# Adafruit_0_96in_128x64_OLED_STEMMA_QT.net
KiCad netlist of a schematic drawn in EAGLE
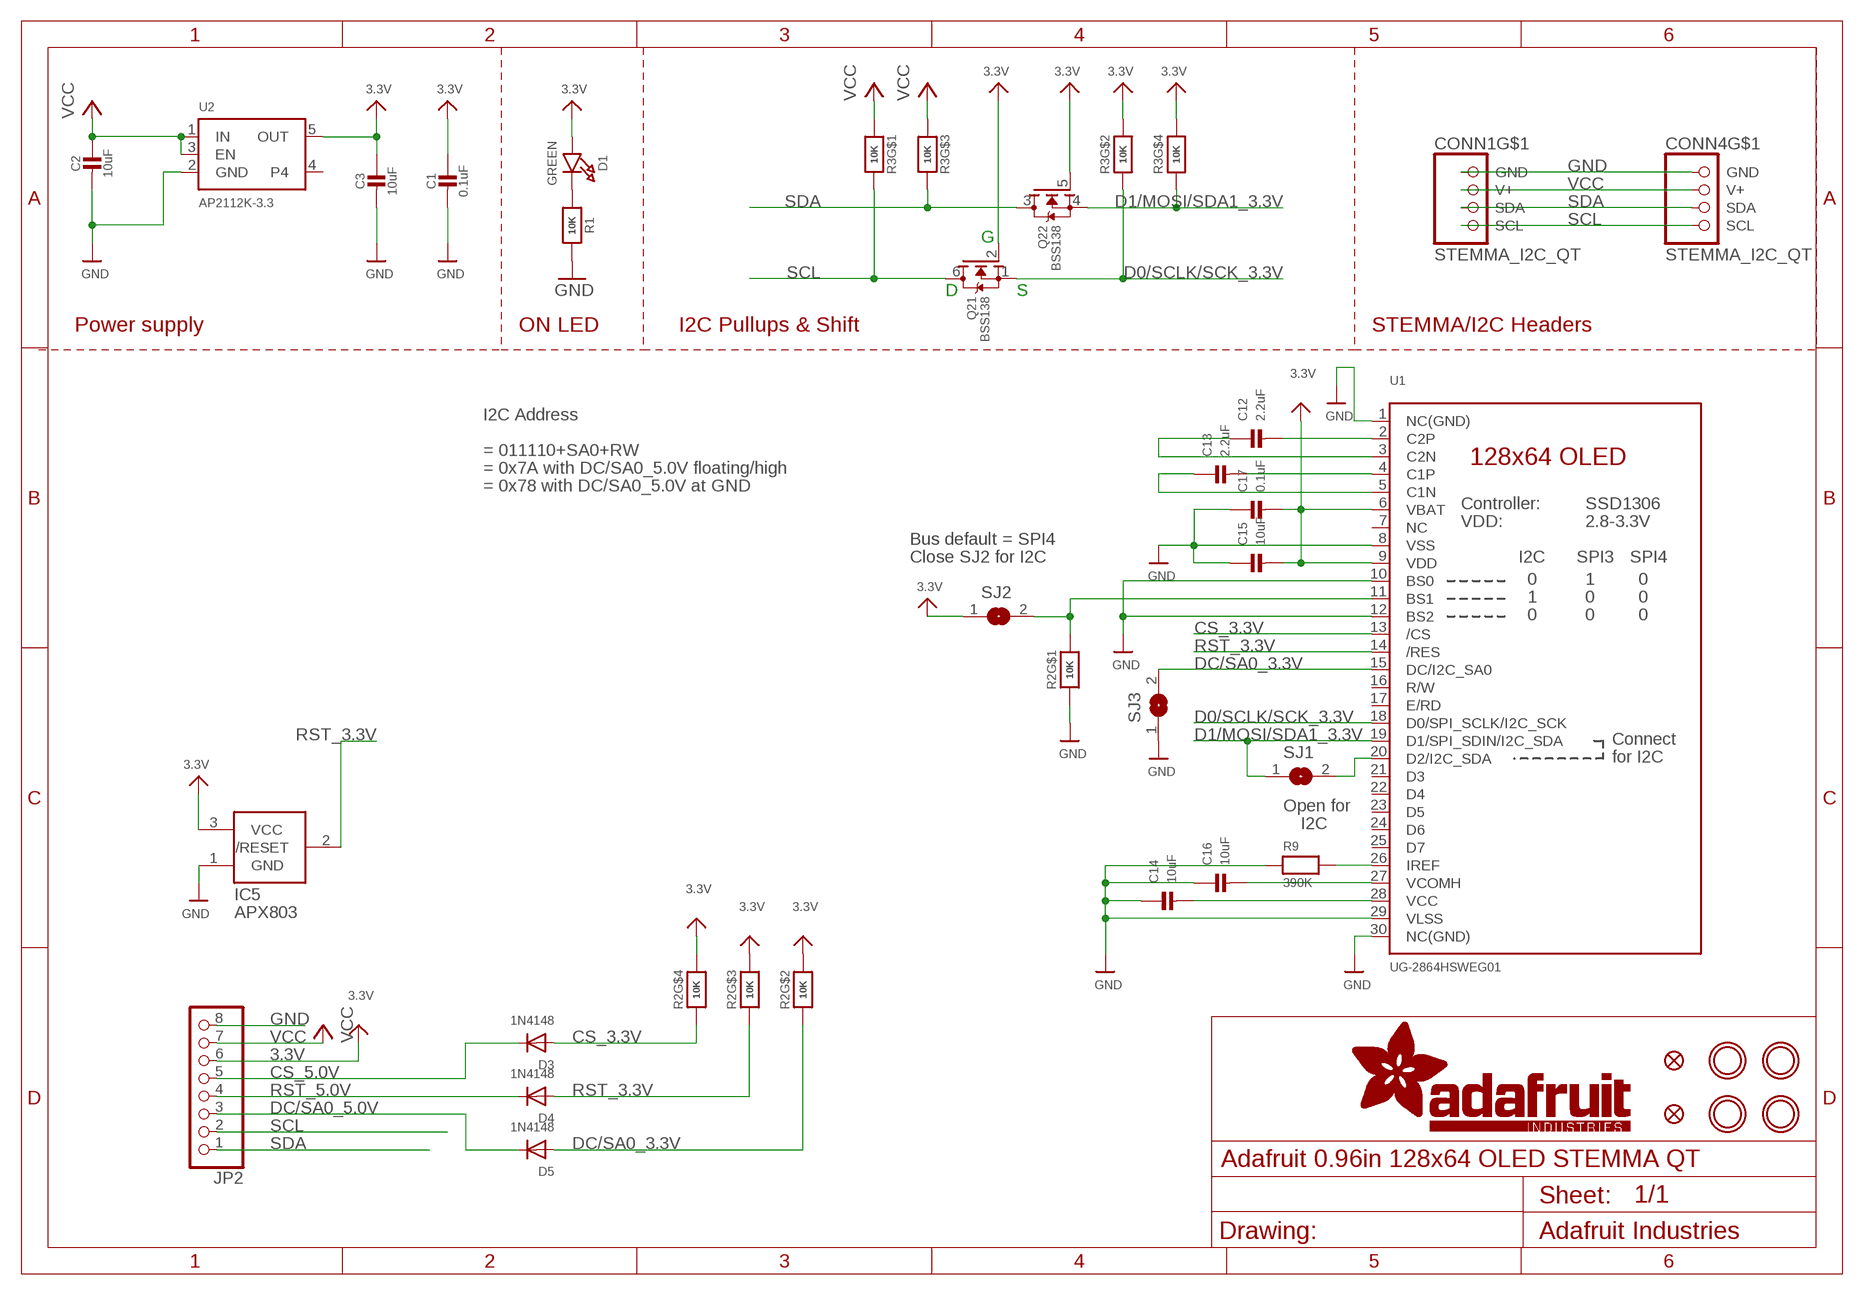
[diagram p0: schematic, sheet 1]

(export (version "E")
  (design (tool "Eeschema 10.0.6"))
  (components
    (comp (ref "C1")
      (value "0.1uF")
      (footprint "eagle-import:0603-NO")
      (libsource (lib "eagle-import") (part "CAP_CERAMIC0603_NO"))
    )
    (comp (ref "C2")
      (value "10uF")
      (footprint "eagle-import:0805-NO")
      (libsource (lib "eagle-import") (part "CAP_CERAMIC0805-NOOUTLINE"))
    )
    (comp (ref "C3")
      (value "10uF")
      (footprint "eagle-import:0805-NO")
      (libsource (lib "eagle-import") (part "CAP_CERAMIC0805-NOOUTLINE"))
    )
    (comp (ref "C12")
      (value "2.2uF")
      (footprint "eagle-import:0805-NO")
      (libsource (lib "eagle-import") (part "CAP_CERAMIC0805-NOOUTLINE"))
    )
    (comp (ref "C13")
      (value "2.2uF")
      (footprint "eagle-import:0805-NO")
      (libsource (lib "eagle-import") (part "CAP_CERAMIC0805-NOOUTLINE"))
    )
    (comp (ref "C14")
      (value "10uF")
      (footprint "eagle-import:0805-NO")
      (libsource (lib "eagle-import") (part "CAP_CERAMIC0805-NOOUTLINE"))
    )
    (comp (ref "C15")
      (value "10uF")
      (footprint "eagle-import:0805-NO")
      (libsource (lib "eagle-import") (part "CAP_CERAMIC0805-NOOUTLINE"))
    )
    (comp (ref "C16")
      (value "10uF")
      (footprint "eagle-import:0805-NO")
      (libsource (lib "eagle-import") (part "CAP_CERAMIC0805-NOOUTLINE"))
    )
    (comp (ref "C17")
      (value "0.1uF")
      (footprint "eagle-import:0603-NO")
      (libsource (lib "eagle-import") (part "CAP_CERAMIC0603_NO"))
    )
    (comp (ref "CONN1")
      (value "STEMMA_I2C_QT")
      (footprint "eagle-import:JST_SH4")
      (libsource (lib "eagle-import") (part "STEMMA_I2C_QT"))
    )
    (comp (ref "CONN4")
      (value "STEMMA_I2C_QT")
      (footprint "eagle-import:JST_SH4")
      (libsource (lib "eagle-import") (part "STEMMA_I2C_QT"))
    )
    (comp (ref "D1")
      (value "GREEN")
      (footprint "eagle-import:CHIPLED_0603_NOOUTLINE")
      (libsource (lib "eagle-import") (part "LED0603_NOOUTLINE"))
    )
    (comp (ref "D3")
      (value "1N4148")
      (footprint "eagle-import:SOD-323")
      (libsource (lib "eagle-import") (part "DIODESOD-323"))
    )
    (comp (ref "D4")
      (value "1N4148")
      (footprint "eagle-import:SOD-323")
      (libsource (lib "eagle-import") (part "DIODESOD-323"))
    )
    (comp (ref "D5")
      (value "1N4148")
      (footprint "eagle-import:SOD-323")
      (libsource (lib "eagle-import") (part "DIODESOD-323"))
    )
    (comp (ref "FID3")
      (value "FIDUCIAL_1MM")
      (footprint "eagle-import:FIDUCIAL_1MM")
      (libsource (lib "eagle-import") (part "FIDUCIAL_1MM"))
    )
    (comp (ref "FID4")
      (value "FIDUCIAL_1MM")
      (footprint "eagle-import:FIDUCIAL_1MM")
      (libsource (lib "eagle-import") (part "FIDUCIAL_1MM"))
    )
    (comp (ref "IC5")
      (value "APX803")
      (footprint "eagle-import:SOT23")
      (libsource (lib "eagle-import") (part "AXP083-SAG"))
    )
    (comp (ref "JP2")
      (value "HEADER-1X870MIL")
      (footprint "eagle-import:1X08_ROUND_70")
      (libsource (lib "eagle-import") (part "HEADER-1X870MIL"))
    )
    (comp (ref "Q2")
      (value "BSS138")
      (footprint "eagle-import:SOT363")
      (libsource (lib "eagle-import") (part "MOSFET-N_DUAL"))
    )
    (comp (ref "R1")
      (value "10K")
      (footprint "eagle-import:0603-NO")
      (libsource (lib "eagle-import") (part "RESISTOR_0603_NOOUT"))
    )
    (comp (ref "R2")
      (value "10K")
      (footprint "eagle-import:RESPACK_4X0603")
      (libsource (lib "eagle-import") (part "RESISTOR_4PACK"))
    )
    (comp (ref "R3")
      (value "10K")
      (footprint "eagle-import:RESPACK_4X0603")
      (libsource (lib "eagle-import") (part "RESISTOR_4PACK"))
    )
    (comp (ref "R9")
      (value "390K")
      (footprint "eagle-import:0603-NO")
      (libsource (lib "eagle-import") (part "RESISTOR_0603_NOOUT"))
    )
    (comp (ref "SJ1")
      (value "SOLDERJUMPERCLOSED")
      (footprint "eagle-import:SOLDERJUMPER_CLOSEDWIRE")
      (libsource (lib "eagle-import") (part "SOLDERJUMPERCLOSED"))
    )
    (comp (ref "SJ2")
      (value "SOLDERJUMPERCLOSED")
      (footprint "eagle-import:SOLDERJUMPER_CLOSEDWIRE")
      (libsource (lib "eagle-import") (part "SOLDERJUMPERCLOSED"))
    )
    (comp (ref "SJ3")
      (value "SOLDERJUMPER")
      (footprint "eagle-import:SOLDERJUMPER_ARROW_NOPASTE")
      (libsource (lib "eagle-import") (part "SOLDERJUMPER"))
    )
    (comp (ref "U$1")
      (value "MOUNTINGHOLE2.5")
      (footprint "eagle-import:MOUNTINGHOLE_2.5_PLATED")
      (libsource (lib "eagle-import") (part "MOUNTINGHOLE2.5"))
    )
    (comp (ref "U$17")
      (value "MOUNTINGHOLE2.5")
      (footprint "eagle-import:MOUNTINGHOLE_2.5_PLATED")
      (libsource (lib "eagle-import") (part "MOUNTINGHOLE2.5"))
    )
    (comp (ref "U$19")
      (value "MOUNTINGHOLE2.5")
      (footprint "eagle-import:MOUNTINGHOLE_2.5_PLATED")
      (libsource (lib "eagle-import") (part "MOUNTINGHOLE2.5"))
    )
    (comp (ref "U$21")
      (value "MOUNTINGHOLE2.5")
      (footprint "eagle-import:MOUNTINGHOLE_2.5_PLATED")
      (libsource (lib "eagle-import") (part "MOUNTINGHOLE2.5"))
    )
    (comp (ref "U1")
      (value "UG-2864HSWEG01")
      (footprint "eagle-import:UG-2864HSWEG01_0.96IN_WRAPAROUND")
      (libsource (lib "eagle-import") (part "DISP_OLED_UG-2864HSWEG010.96{dblquote}"))
    )
    (comp (ref "U2")
      (value "AP2112K-3.3")
      (footprint "eagle-import:SOT23-5")
      (libsource (lib "eagle-import") (part "VREG_SOT23-5"))
    )
  )
  (nets
    (net (code "1") (name "/CS_3.3V") (class "Default")
      (node (ref "D3") (pin "A") (pinfunction "A_A") (pintype "passive"))
      (node (ref "R2") (pin "4") (pinfunction "1_4") (pintype "passive"))
      (node (ref "U1") (pin "13") (pinfunction "/CS_13") (pintype "input"))
    )
    (net (code "2") (name "/CS_5.0V") (class "Default")
      (node (ref "D3") (pin "C") (pinfunction "C_C") (pintype "passive"))
      (node (ref "JP2") (pin "5") (pinfunction "5_5") (pintype "passive"))
    )
    (net (code "3") (name "/D0{slash}SCLK{slash}SCK_3.3V") (class "Default")
      (node (ref "Q2") (pin "1") (pinfunction "S_1") (pintype "bidirectional"))
      (node (ref "R3") (pin "7") (pinfunction "2_7") (pintype "passive"))
      (node (ref "U1") (pin "18") (pinfunction "D0/SPI_SCLK/I2C_SCK_18") (pintype "bidirectional"))
    )
    (net (code "4") (name "/D1{slash}MOSI{slash}SDA1_3.3V") (class "Default")
      (node (ref "Q2") (pin "4") (pinfunction "S_4") (pintype "bidirectional"))
      (node (ref "R3") (pin "5") (pinfunction "2_5") (pintype "passive"))
      (node (ref "SJ1") (pin "1") (pinfunction "1_1") (pintype "passive"))
      (node (ref "U1") (pin "19") (pinfunction "D1/SPI_SDIN/I2C_SDA_19") (pintype "bidirectional"))
    )
    (net (code "5") (name "/DC{slash}SA0_3.3V") (class "Default")
      (node (ref "D5") (pin "A") (pinfunction "A_A") (pintype "passive"))
      (node (ref "R2") (pin "2") (pinfunction "1_2") (pintype "passive"))
      (node (ref "SJ3") (pin "2") (pinfunction "2_2") (pintype "passive"))
      (node (ref "U1") (pin "15") (pinfunction "DC/I2C_SA0_15") (pintype "input"))
    )
    (net (code "6") (name "/DC{slash}SA0_5.0V") (class "Default")
      (node (ref "D5") (pin "C") (pinfunction "C_C") (pintype "passive"))
      (node (ref "JP2") (pin "3") (pinfunction "3_3") (pintype "passive"))
    )
    (net (code "7") (name "/RST_3.3V") (class "Default")
      (node (ref "D4") (pin "A") (pinfunction "A_A") (pintype "passive"))
      (node (ref "IC5") (pin "2") (pinfunction "/RESET_2") (pintype "output"))
      (node (ref "R2") (pin "3") (pinfunction "1_3") (pintype "passive"))
      (node (ref "U1") (pin "14") (pinfunction "/RES_14") (pintype "input"))
    )
    (net (code "8") (name "/RST_5.0V") (class "Default")
      (node (ref "D4") (pin "C") (pinfunction "C_C") (pintype "passive"))
      (node (ref "JP2") (pin "4") (pinfunction "4_4") (pintype "passive"))
    )
    (net (code "9") (name "/SCL") (class "Default")
      (node (ref "CONN1") (pin "4") (pinfunction "SCL_4") (pintype "passive"))
      (node (ref "CONN4") (pin "4") (pinfunction "SCL_4") (pintype "passive"))
      (node (ref "JP2") (pin "2") (pinfunction "2_2") (pintype "passive"))
      (node (ref "Q2") (pin "6") (pinfunction "D_6") (pintype "bidirectional"))
      (node (ref "R3") (pin "8") (pinfunction "2_8") (pintype "passive"))
    )
    (net (code "10") (name "/SDA") (class "Default")
      (node (ref "CONN1") (pin "3") (pinfunction "SDA_3") (pintype "passive"))
      (node (ref "CONN4") (pin "3") (pinfunction "SDA_3") (pintype "passive"))
      (node (ref "JP2") (pin "1") (pinfunction "1_1") (pintype "passive"))
      (node (ref "Q2") (pin "3") (pinfunction "D_3") (pintype "bidirectional"))
      (node (ref "R3") (pin "6") (pinfunction "2_6") (pintype "passive"))
    )
    (net (code "11") (name "3.3V") (class "Default")
      (node (ref "C1") (pin "1") (pinfunction "1_1") (pintype "passive"))
      (node (ref "C15") (pin "2") (pinfunction "2_2") (pintype "passive"))
      (node (ref "C17") (pin "2") (pinfunction "2_2") (pintype "passive"))
      (node (ref "C3") (pin "1") (pinfunction "1_1") (pintype "passive"))
      (node (ref "D1") (pin "A") (pinfunction "A_A") (pintype "passive"))
      (node (ref "IC5") (pin "3") (pinfunction "VCC_3") (pintype "power_in"))
      (node (ref "JP2") (pin "6") (pinfunction "6_6") (pintype "passive"))
      (node (ref "Q2") (pin "2") (pinfunction "G_2") (pintype "bidirectional"))
      (node (ref "Q2") (pin "5") (pinfunction "G_5") (pintype "bidirectional"))
      (node (ref "R2") (pin "5") (pinfunction "2_5") (pintype "passive"))
      (node (ref "R2") (pin "6") (pinfunction "2_6") (pintype "passive"))
      (node (ref "R2") (pin "7") (pinfunction "2_7") (pintype "passive"))
      (node (ref "R3") (pin "2") (pinfunction "1_2") (pintype "passive"))
      (node (ref "R3") (pin "4") (pinfunction "1_4") (pintype "passive"))
      (node (ref "SJ2") (pin "1") (pinfunction "1_1") (pintype "passive"))
      (node (ref "U1") (pin "6") (pinfunction "VBAT_6") (pintype "input"))
      (node (ref "U1") (pin "9") (pinfunction "VDD_9") (pintype "power_in"))
      (node (ref "U2") (pin "5") (pinfunction "OUT_5") (pintype "power_in"))
    )
    (net (code "12") (name "GND") (class "Default")
      (node (ref "C1") (pin "2") (pinfunction "2_2") (pintype "passive"))
      (node (ref "C14") (pin "1") (pinfunction "1_1") (pintype "passive"))
      (node (ref "C15") (pin "1") (pinfunction "1_1") (pintype "passive"))
      (node (ref "C16") (pin "1") (pinfunction "1_1") (pintype "passive"))
      (node (ref "C17") (pin "1") (pinfunction "1_1") (pintype "passive"))
      (node (ref "C2") (pin "2") (pinfunction "2_2") (pintype "passive"))
      (node (ref "C3") (pin "2") (pinfunction "2_2") (pintype "passive"))
      (node (ref "CONN1") (pin "1") (pinfunction "GND_1") (pintype "passive"))
      (node (ref "CONN4") (pin "1") (pinfunction "GND_1") (pintype "passive"))
      (node (ref "IC5") (pin "1") (pinfunction "GND_1") (pintype "power_in"))
      (node (ref "JP2") (pin "8") (pinfunction "8_8") (pintype "passive"))
      (node (ref "R1") (pin "2") (pinfunction "2_2") (pintype "passive"))
      (node (ref "R2") (pin "1") (pinfunction "1_1") (pintype "passive"))
      (node (ref "R9") (pin "1") (pinfunction "1_1") (pintype "passive"))
      (node (ref "SJ3") (pin "1") (pinfunction "1_1") (pintype "passive"))
      (node (ref "U1") (pin "1") (pinfunction "NC(GND)_1") (pintype "input"))
      (node (ref "U1") (pin "10") (pinfunction "BS0_10") (pintype "input"))
      (node (ref "U1") (pin "12") (pinfunction "BS2_12") (pintype "input"))
      (node (ref "U1") (pin "29") (pinfunction "VLSS_29") (pintype "power_in"))
      (node (ref "U1") (pin "30") (pinfunction "NC(GND)_30") (pintype "input"))
      (node (ref "U1") (pin "8") (pinfunction "VSS_8") (pintype "power_in"))
      (node (ref "U2") (pin "2") (pinfunction "GND_2") (pintype "power_in"))
    )
    (net (code "13") (name "Net-(D1-PadC)") (class "Default")
      (node (ref "D1") (pin "C") (pinfunction "C_C") (pintype "passive"))
      (node (ref "R1") (pin "1") (pinfunction "1_1") (pintype "passive"))
    )
    (net (code "14") (name "Net-(R2A-2)") (class "Default")
      (node (ref "R2") (pin "8") (pinfunction "2_8") (pintype "passive"))
      (node (ref "SJ2") (pin "2") (pinfunction "2_2") (pintype "passive"))
      (node (ref "U1") (pin "11") (pinfunction "BS1_11") (pintype "input"))
    )
    (net (code "15") (name "Net-(U1-C1N)") (class "Default")
      (node (ref "C13") (pin "1") (pinfunction "1_1") (pintype "passive"))
      (node (ref "U1") (pin "5") (pinfunction "C1N_5") (pintype "input"))
    )
    (net (code "16") (name "Net-(U1-C1P)") (class "Default")
      (node (ref "C13") (pin "2") (pinfunction "2_2") (pintype "passive"))
      (node (ref "U1") (pin "4") (pinfunction "C1P_4") (pintype "input"))
    )
    (net (code "17") (name "Net-(U1-C2N)") (class "Default")
      (node (ref "C12") (pin "1") (pinfunction "1_1") (pintype "passive"))
      (node (ref "U1") (pin "3") (pinfunction "C2N_3") (pintype "input"))
    )
    (net (code "18") (name "Net-(U1-C2P)") (class "Default")
      (node (ref "C12") (pin "2") (pinfunction "2_2") (pintype "passive"))
      (node (ref "U1") (pin "2") (pinfunction "C2P_2") (pintype "input"))
    )
    (net (code "19") (name "Net-(U1-D2{slash}I2C_SDA)") (class "Default")
      (node (ref "SJ1") (pin "2") (pinfunction "2_2") (pintype "passive"))
      (node (ref "U1") (pin "20") (pinfunction "D2/I2C_SDA_20") (pintype "bidirectional"))
    )
    (net (code "20") (name "Net-(U1-IREF)") (class "Default")
      (node (ref "R9") (pin "2") (pinfunction "2_2") (pintype "passive"))
      (node (ref "U1") (pin "26") (pinfunction "IREF_26") (pintype "input"))
    )
    (net (code "21") (name "Net-(U1-VCC)") (class "Default")
      (node (ref "C14") (pin "2") (pinfunction "2_2") (pintype "passive"))
      (node (ref "U1") (pin "28") (pinfunction "VCC_28") (pintype "power_in"))
    )
    (net (code "22") (name "Net-(U1-VCOMH)") (class "Default")
      (node (ref "C16") (pin "2") (pinfunction "2_2") (pintype "passive"))
      (node (ref "U1") (pin "27") (pinfunction "VCOMH_27") (pintype "output"))
    )
    (net (code "23") (name "VCC") (class "Default")
      (node (ref "C2") (pin "1") (pinfunction "1_1") (pintype "passive"))
      (node (ref "CONN1") (pin "2") (pinfunction "V+_2") (pintype "passive"))
      (node (ref "CONN4") (pin "2") (pinfunction "V+_2") (pintype "passive"))
      (node (ref "JP2") (pin "7") (pinfunction "7_7") (pintype "passive"))
      (node (ref "R3") (pin "1") (pinfunction "1_1") (pintype "passive"))
      (node (ref "R3") (pin "3") (pinfunction "1_3") (pintype "passive"))
      (node (ref "U2") (pin "1") (pinfunction "IN_1") (pintype "power_in"))
      (node (ref "U2") (pin "3") (pinfunction "EN_3") (pintype "input"))
    )
    (net (code "24") (name "unconnected-(U1-D3-Pad21)") (class "Default")
      (node (ref "U1") (pin "21") (pinfunction "D3_21") (pintype "bidirectional"))
    )
    (net (code "25") (name "unconnected-(U1-D4-Pad22)") (class "Default")
      (node (ref "U1") (pin "22") (pinfunction "D4_22") (pintype "bidirectional"))
    )
    (net (code "26") (name "unconnected-(U1-D5-Pad23)") (class "Default")
      (node (ref "U1") (pin "23") (pinfunction "D5_23") (pintype "bidirectional"))
    )
    (net (code "27") (name "unconnected-(U1-D6-Pad24)") (class "Default")
      (node (ref "U1") (pin "24") (pinfunction "D6_24") (pintype "bidirectional"))
    )
    (net (code "28") (name "unconnected-(U1-D7-Pad25)") (class "Default")
      (node (ref "U1") (pin "25") (pinfunction "D7_25") (pintype "bidirectional"))
    )
    (net (code "29") (name "unconnected-(U1-E{slash}RD-Pad17)") (class "Default")
      (node (ref "U1") (pin "17") (pinfunction "E/RD_17") (pintype "input"))
    )
    (net (code "30") (name "unconnected-(U1-NC-Pad7)") (class "Default")
      (node (ref "U1") (pin "7") (pinfunction "NC_7") (pintype "no_connect"))
    )
    (net (code "31") (name "unconnected-(U1-R{slash}W-Pad16)") (class "Default")
      (node (ref "U1") (pin "16") (pinfunction "R/W_16") (pintype "input"))
    )
    (net (code "32") (name "unconnected-(U2-P4-Pad4)") (class "Default")
      (node (ref "U2") (pin "4") (pinfunction "P4_4") (pintype "bidirectional"))
    )
  )
)
